# INPUT_OUPUT.net
KiCad netlist of a schematic drawn in Altium Designer
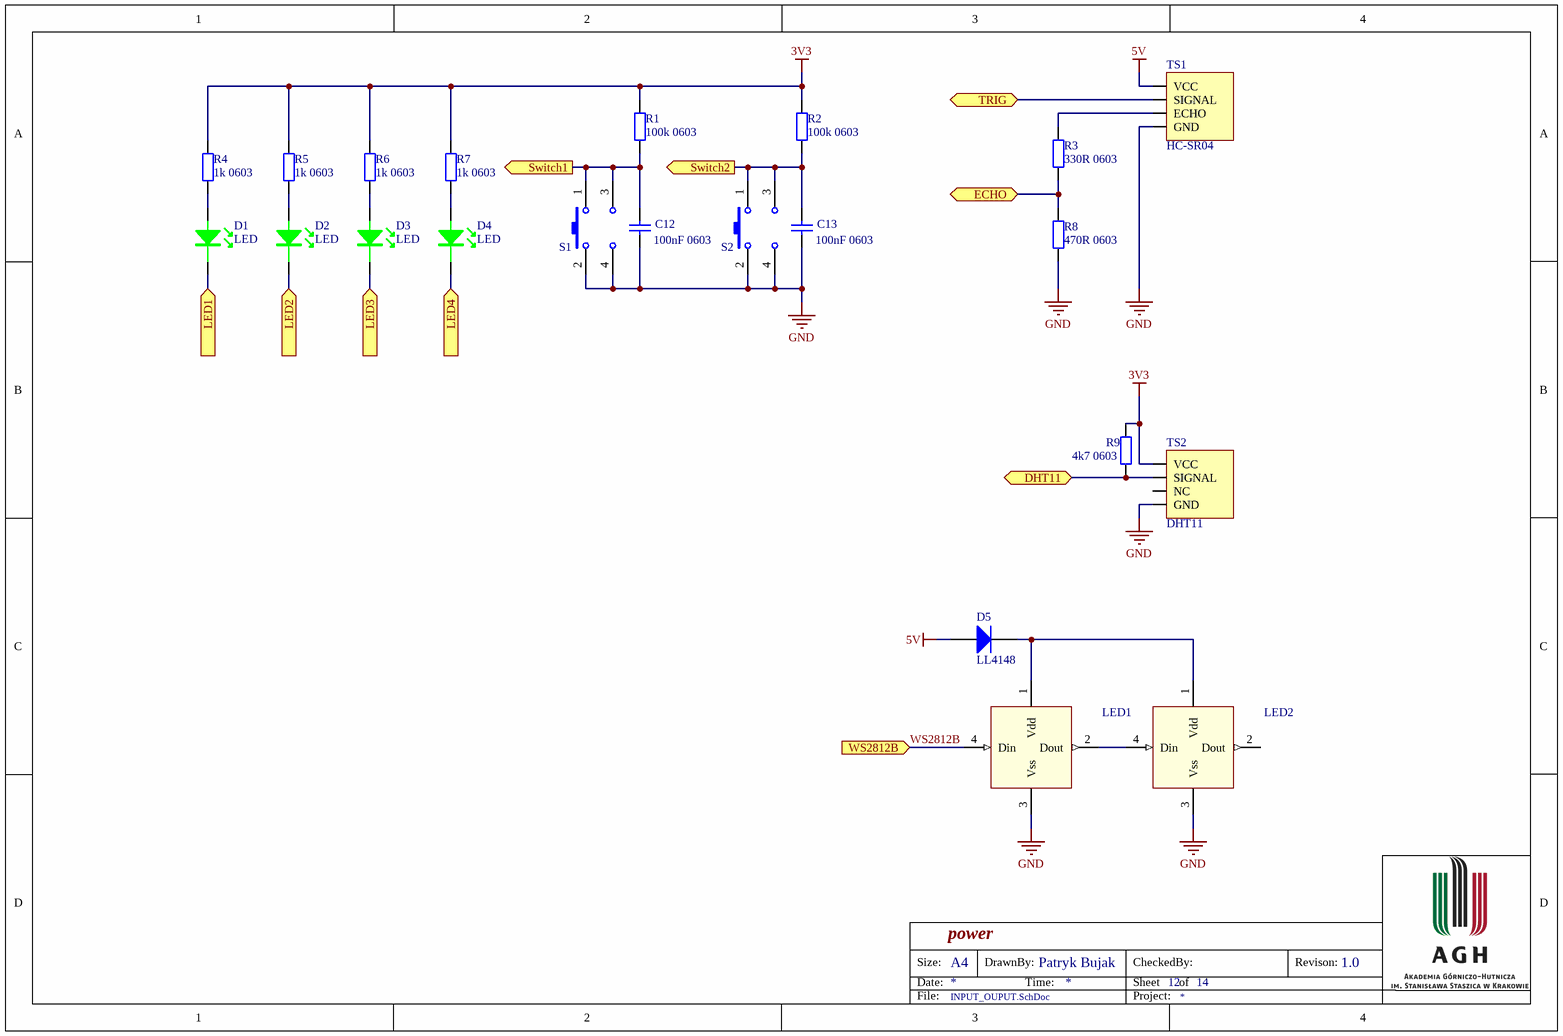
[diagram p0: INPUT_OUPUT.SchDoc]

(export (version "E")
  (design (tool "Eeschema 10.0.6"))
  (components
    (comp (ref "C12")
      (value "100nF 0603")
      (footprint "C_0603")
      (description "Generic capacitor")
      (fields (field (name "VOLTAGE") "25V"))
      (libsource (lib "Miscellaneous Devices") (part "Cap"))
    )
    (comp (ref "C13")
      (value "100nF 0603")
      (footprint "C_0603")
      (description "Generic capacitor")
      (fields (field (name "VOLTAGE") "25V"))
      (libsource (lib "Miscellaneous Devices") (part "Cap"))
    )
    (comp (ref "D1")
      (value "LED")
      (footprint "LED_1206_GREEN")
      (libsource (lib "Patryk_ROZNE") (part "LED_GREEN"))
    )
    (comp (ref "D2")
      (value "LED")
      (footprint "LED_1206_GREEN")
      (libsource (lib "Patryk_ROZNE") (part "LED_GREEN"))
    )
    (comp (ref "D3")
      (value "LED")
      (footprint "LED_1206_GREEN")
      (libsource (lib "Patryk_ROZNE") (part "LED_GREEN"))
    )
    (comp (ref "D4")
      (value "LED")
      (footprint "LED_1206_GREEN")
      (libsource (lib "Patryk_ROZNE") (part "LED_GREEN"))
    )
    (comp (ref "D5")
      (value "LL4148")
      (footprint "MINIMELF_DIODA_REFLOW")
      (description "Default Diode")
      (fields (field (name "PUBLISHER") "Altium Limited"))
      (libsource (lib "Miscellaneous Devices") (part "Diode"))
    )
    (comp (ref "LED1")
      (value "WS2812B")
      (footprint "WS2812B")
      (libsource (lib "Patryk_ROZNE") (part "WS2812B"))
    )
    (comp (ref "LED2")
      (value "WS2812B")
      (footprint "WS2812B")
      (libsource (lib "Patryk_ROZNE") (part "WS2812B"))
    )
    (comp (ref "R1")
      (value "100k 0603")
      (footprint "R_0603")
      (description "Resistor")
      (libsource (lib "") (part "Res2_1"))
    )
    (comp (ref "R2")
      (value "100k 0603")
      (footprint "R_0603")
      (description "Resistor")
      (libsource (lib "") (part "Res2_1"))
    )
    (comp (ref "R3")
      (value "330R 0603")
      (footprint "R_0603")
      (description "Resistor")
      (libsource (lib "") (part "Res2_1"))
    )
    (comp (ref "R4")
      (value "1k 0603")
      (footprint "R_0603")
      (description "Resistor")
      (libsource (lib "") (part "Res2_1"))
    )
    (comp (ref "R5")
      (value "1k 0603")
      (footprint "R_0603")
      (description "Resistor")
      (libsource (lib "") (part "Res2_1"))
    )
    (comp (ref "R6")
      (value "1k 0603")
      (footprint "R_0603")
      (description "Resistor")
      (libsource (lib "") (part "Res2_1"))
    )
    (comp (ref "R7")
      (value "1k 0603")
      (footprint "R_0603")
      (description "Resistor")
      (libsource (lib "") (part "Res2_1"))
    )
    (comp (ref "R8")
      (value "470R 0603")
      (footprint "R_0603")
      (description "Resistor")
      (libsource (lib "") (part "Res2_1"))
    )
    (comp (ref "R9")
      (value "4k7 0603")
      (footprint "R_0603")
      (description "Resistor")
      (libsource (lib "Miscellaneous Devices") (part "Res2"))
    )
    (comp (ref "S1")
      (value "tact_switch")
      (footprint "RESET-1")
      (description "Switch")
      (fields (field (name "MANUFACTURER") "Generic Components") (field (name "PUBLISHER") "Altium Limited"))
      (libsource (lib "Patryk_ROZNE") (part "tact_switch"))
    )
    (comp (ref "S2")
      (value "tact_switch")
      (footprint "RESET-1")
      (description "Switch")
      (fields (field (name "MANUFACTURER") "Generic Components") (field (name "PUBLISHER") "Altium Limited"))
      (libsource (lib "Patryk_ROZNE") (part "tact_switch"))
    )
    (comp (ref "TS1") (value "HC-SR04") (footprint "HC-SR04") (libsource (lib "") (part "DHT11_1")))
    (comp (ref "TS2") (value "DHT11") (footprint "DHT11") (libsource (lib "Patryk_ROZNE") (part "DHT11")))
  )
  (nets
    (net (code "1") (name "/DHT11") (class "Default")
      (node (ref "R9") (pin "1") (pinfunction "1_1") (pintype "passive"))
      (node (ref "TS2") (pin "2") (pinfunction "SIGNAL_2") (pintype "passive"))
    )
    (net (code "2") (name "/ECHO") (class "Default")
      (node (ref "R3") (pin "1") (pinfunction "1_1") (pintype "passive"))
      (node (ref "R8") (pin "2") (pinfunction "2_2") (pintype "passive"))
    )
    (net (code "3") (name "/LED1") (class "Default")
      (node (ref "D1") (pin "2") (pinfunction "K_2") (pintype "passive"))
    )
    (net (code "4") (name "/LED2") (class "Default")
      (node (ref "D2") (pin "2") (pinfunction "K_2") (pintype "passive"))
    )
    (net (code "5") (name "/LED3") (class "Default")
      (node (ref "D3") (pin "2") (pinfunction "K_2") (pintype "passive"))
    )
    (net (code "6") (name "/LED4") (class "Default")
      (node (ref "D4") (pin "2") (pinfunction "K_2") (pintype "passive"))
    )
    (net (code "7") (name "/Switch1") (class "Default")
      (node (ref "C12") (pin "1") (pinfunction "1_1") (pintype "passive"))
      (node (ref "R1") (pin "1") (pinfunction "1_1") (pintype "passive"))
      (node (ref "S1") (pin "1") (pinfunction "1_1") (pintype "passive"))
      (node (ref "S1") (pin "3") (pinfunction "3_3") (pintype "passive"))
    )
    (net (code "8") (name "/Switch2") (class "Default")
      (node (ref "C13") (pin "1") (pinfunction "1_1") (pintype "passive"))
      (node (ref "R2") (pin "1") (pinfunction "1_1") (pintype "passive"))
      (node (ref "S2") (pin "1") (pinfunction "1_1") (pintype "passive"))
      (node (ref "S2") (pin "3") (pinfunction "3_3") (pintype "passive"))
    )
    (net (code "9") (name "/TRIG") (class "Default")
      (node (ref "TS1") (pin "3") (pinfunction "SIGNAL_3") (pintype "passive"))
    )
    (net (code "10") (name "/WS2812B") (class "Default")
      (node (ref "LED1") (pin "4") (pinfunction "Din_4") (pintype "input"))
    )
    (net (code "11") (name "3V3") (class "Default")
      (node (ref "R1") (pin "2") (pinfunction "2_2") (pintype "passive"))
      (node (ref "R2") (pin "2") (pinfunction "2_2") (pintype "passive"))
      (node (ref "R4") (pin "2") (pinfunction "2_2") (pintype "passive"))
      (node (ref "R5") (pin "2") (pinfunction "2_2") (pintype "passive"))
      (node (ref "R6") (pin "2") (pinfunction "2_2") (pintype "passive"))
      (node (ref "R7") (pin "2") (pinfunction "2_2") (pintype "passive"))
      (node (ref "R9") (pin "2") (pinfunction "2_2") (pintype "passive"))
      (node (ref "TS2") (pin "1") (pinfunction "VCC_1") (pintype "passive"))
    )
    (net (code "12") (name "5V") (class "Default")
      (node (ref "D5") (pin "1") (pinfunction "A_1") (pintype "passive"))
      (node (ref "TS1") (pin "4") (pinfunction "VCC_4") (pintype "passive"))
    )
    (net (code "13") (name "GND") (class "Default")
      (node (ref "C12") (pin "2") (pinfunction "2_2") (pintype "passive"))
      (node (ref "C13") (pin "2") (pinfunction "2_2") (pintype "passive"))
      (node (ref "LED1") (pin "3") (pinfunction "Vss_3") (pintype "power_in"))
      (node (ref "LED2") (pin "3") (pinfunction "Vss_3") (pintype "power_in"))
      (node (ref "R8") (pin "1") (pinfunction "1_1") (pintype "passive"))
      (node (ref "S1") (pin "2") (pinfunction "2_2") (pintype "passive"))
      (node (ref "S1") (pin "4") (pinfunction "4_4") (pintype "passive"))
      (node (ref "S2") (pin "2") (pinfunction "2_2") (pintype "passive"))
      (node (ref "S2") (pin "4") (pinfunction "4_4") (pintype "passive"))
      (node (ref "TS1") (pin "1") (pinfunction "GND_1") (pintype "passive"))
      (node (ref "TS2") (pin "4") (pinfunction "GND_4") (pintype "passive"))
    )
    (net (code "14") (name "Net-(D1-A)") (class "Default")
      (node (ref "D1") (pin "1") (pinfunction "A_1") (pintype "passive"))
      (node (ref "R4") (pin "1") (pinfunction "1_1") (pintype "passive"))
    )
    (net (code "15") (name "Net-(D2-A)") (class "Default")
      (node (ref "D2") (pin "1") (pinfunction "A_1") (pintype "passive"))
      (node (ref "R5") (pin "1") (pinfunction "1_1") (pintype "passive"))
    )
    (net (code "16") (name "Net-(D3-A)") (class "Default")
      (node (ref "D3") (pin "1") (pinfunction "A_1") (pintype "passive"))
      (node (ref "R6") (pin "1") (pinfunction "1_1") (pintype "passive"))
    )
    (net (code "17") (name "Net-(D4-A)") (class "Default")
      (node (ref "D4") (pin "1") (pinfunction "A_1") (pintype "passive"))
      (node (ref "R7") (pin "1") (pinfunction "1_1") (pintype "passive"))
    )
    (net (code "18") (name "Net-(D5-K)") (class "Default")
      (node (ref "D5") (pin "2") (pinfunction "K_2") (pintype "passive"))
      (node (ref "LED1") (pin "1") (pinfunction "Vdd_1") (pintype "power_in"))
      (node (ref "LED2") (pin "1") (pinfunction "Vdd_1") (pintype "power_in"))
    )
    (net (code "19") (name "Net-(LED1-Dout)") (class "Default")
      (node (ref "LED1") (pin "2") (pinfunction "Dout_2") (pintype "output"))
      (node (ref "LED2") (pin "4") (pinfunction "Din_4") (pintype "input"))
    )
    (net (code "20") (name "Net-(TS1-ECHO)") (class "Default")
      (node (ref "R3") (pin "2") (pinfunction "2_2") (pintype "passive"))
      (node (ref "TS1") (pin "2") (pinfunction "ECHO_2") (pintype "passive"))
    )
    (net (code "21") (name "unconnected-(LED2-Dout-Pad2)") (class "Default")
      (node (ref "LED2") (pin "2") (pinfunction "Dout_2") (pintype "output"))
    )
    (net (code "22") (name "unconnected-(TS2-NC-Pad3)") (class "Default")
      (node (ref "TS2") (pin "3") (pinfunction "NC_3") (pintype "passive"))
    )
  )
)
